# EXM_Safety_Board_-_Rev_A1.net
KiCad netlist of a schematic drawn in EAGLE
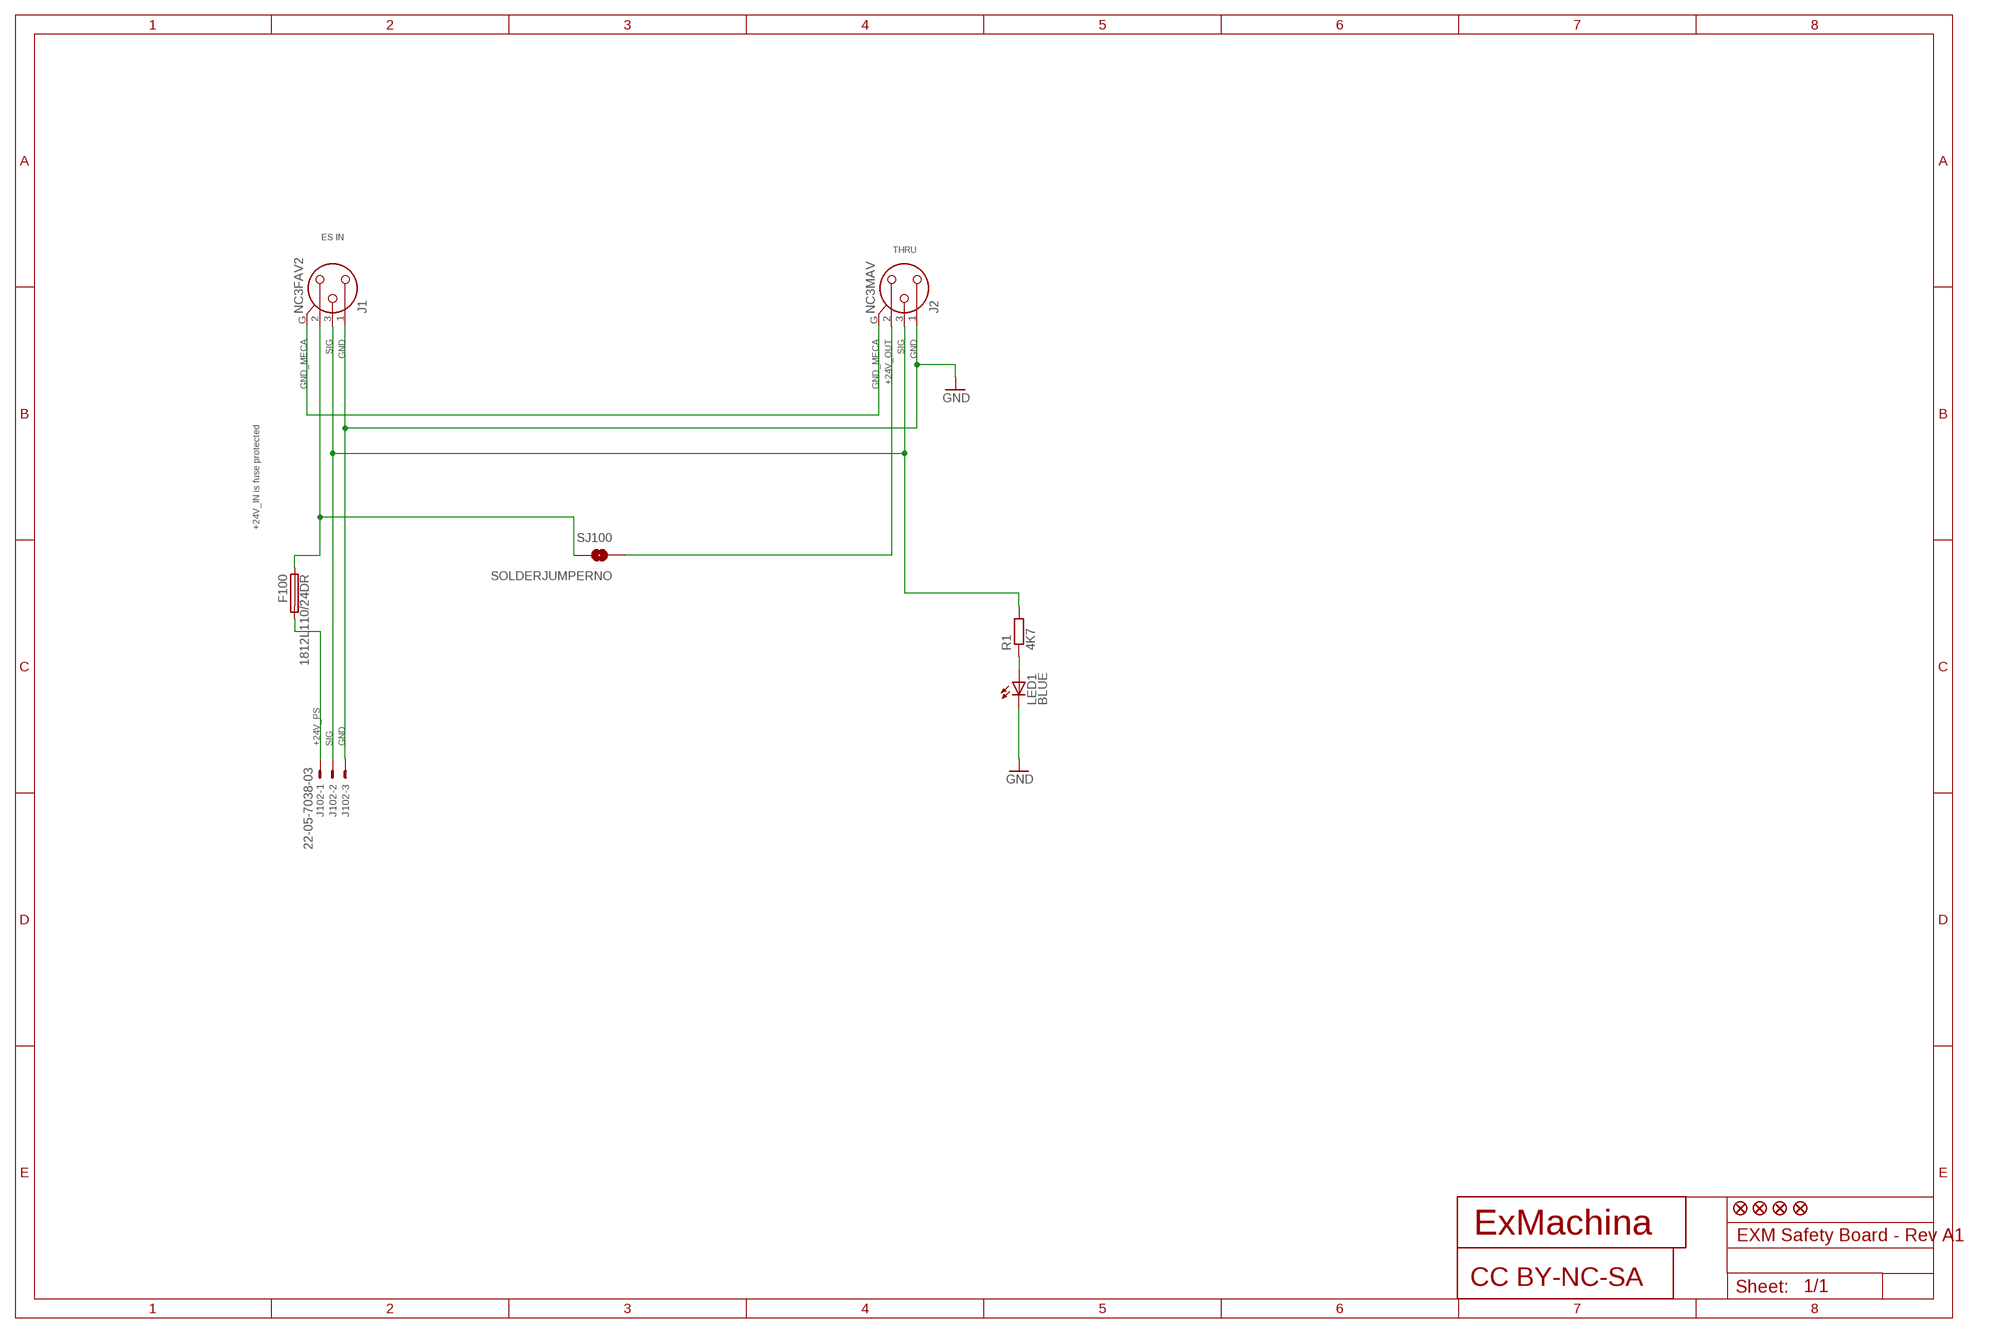
[diagram p0: schematic, sheet 1]

(export (version "E")
  (design (tool "Eeschema 10.0.6"))
  (components
    (comp (ref "CC100")
      (value "CC-BY-NC-SA")
      (footprint "eagle-import:CC-BY-NC-SA")
      (libsource (lib "eagle-import") (part "CC-BY-NC-SA"))
    )
    (comp (ref "F100")
      (value "1812L110/24DR")
      (footprint "eagle-import:LITTLEFUSE_SMD")
      (libsource (lib "eagle-import") (part "1812L110/24DR"))
    )
    (comp (ref "J1")
      (value "NC3FAV2")
      (footprint "eagle-import:NC3FAV2")
      (fields (field (name "MF") "NEUTRIK"))
      (libsource (lib "eagle-import") (part "NC3FAV2"))
    )
    (comp (ref "J2")
      (value "NC3MAV")
      (footprint "eagle-import:NC3MAV")
      (fields (field (name "MF") "FARNELL"))
      (libsource (lib "eagle-import") (part "NC3MAV"))
    )
    (comp (ref "J102")
      (value "22-05-7038-03")
      (footprint "eagle-import:7395-03")
      (libsource (lib "eagle-import") (part "22-?-0305-7038"))
    )
    (comp (ref "JP100")
      (value "FIDUCIAL1X2")
      (footprint "eagle-import:FIDUCIAL-1X2")
      (libsource (lib "eagle-import") (part "FIDUCIAL1X2"))
    )
    (comp (ref "JP101")
      (value "FIDUCIAL1X2")
      (footprint "eagle-import:FIDUCIAL-1X2")
      (libsource (lib "eagle-import") (part "FIDUCIAL1X2"))
    )
    (comp (ref "JP102")
      (value "FIDUCIAL1X2")
      (footprint "eagle-import:FIDUCIAL-1X2")
      (libsource (lib "eagle-import") (part "FIDUCIAL1X2"))
    )
    (comp (ref "JP103")
      (value "FIDUCIAL1X2")
      (footprint "eagle-import:FIDUCIAL-1X2")
      (libsource (lib "eagle-import") (part "FIDUCIAL1X2"))
    )
    (comp (ref "LED1")
      (value "BLUE")
      (footprint "eagle-import:CHIPLED_0603")
      (fields (field (name "MPN") "OVS-0603"))
      (libsource (lib "eagle-import") (part "LEDCHIPLED_0603"))
    )
    (comp (ref "R1")
      (value "4K7")
      (footprint "eagle-import:R0603")
      (fields (field (name "MPN") "RC0603FR-074K7L"))
      (libsource (lib "eagle-import") (part "R-EU_R0603"))
    )
    (comp (ref "SJ100")
      (value "SOLDERJUMPERNO")
      (footprint "eagle-import:SJ_2S-NO")
      (libsource (lib "eagle-import") (part "SOLDERJUMPERNO"))
    )
    (comp (ref "T100")
      (value "EXMACHINA-LOGO-NAME")
      (footprint "eagle-import:EXM-LOGO-BASELINE")
      (libsource (lib "eagle-import") (part "EXMACHINA-LOGO-NAME"))
    )
  )
  (nets
    (net (code "1") (name "/+24V_OUT") (class "Default")
      (node (ref "J2") (pin "2") (pinfunction "2_2") (pintype "passive"))
      (node (ref "SJ100") (pin "1") (pinfunction "1_1") (pintype "passive"))
    )
    (net (code "2") (name "/+24V_PS") (class "Default")
      (node (ref "F100") (pin "2") (pinfunction "2_2") (pintype "passive"))
      (node (ref "J102") (pin "1") (pinfunction "S_1") (pintype "passive"))
    )
    (net (code "3") (name "/GND_MECA") (class "Default")
      (node (ref "J1") (pin "G") (pinfunction "G_G") (pintype "passive"))
      (node (ref "J2") (pin "G") (pinfunction "G_G") (pintype "passive"))
    )
    (net (code "4") (name "/SIG") (class "Default")
      (node (ref "J1") (pin "3") (pinfunction "3_3") (pintype "passive"))
      (node (ref "J102") (pin "2") (pinfunction "S_2") (pintype "passive"))
      (node (ref "J2") (pin "3") (pinfunction "3_3") (pintype "passive"))
      (node (ref "R1") (pin "2") (pinfunction "2_2") (pintype "passive"))
    )
    (net (code "5") (name "GND") (class "Default")
      (node (ref "J1") (pin "1") (pinfunction "1_1") (pintype "passive"))
      (node (ref "J102") (pin "3") (pinfunction "S_3") (pintype "passive"))
      (node (ref "J2") (pin "1") (pinfunction "1_1") (pintype "passive"))
      (node (ref "LED1") (pin "C") (pinfunction "C_C") (pintype "passive"))
    )
    (net (code "6") (name "Net-(F100-Pad1)") (class "Default")
      (node (ref "F100") (pin "1") (pinfunction "1_1") (pintype "passive"))
      (node (ref "J1") (pin "2") (pinfunction "2_2") (pintype "passive"))
      (node (ref "SJ100") (pin "2") (pinfunction "2_2") (pintype "passive"))
    )
    (net (code "7") (name "Net-(LED1-PadA)") (class "Default")
      (node (ref "LED1") (pin "A") (pinfunction "A_A") (pintype "passive"))
      (node (ref "R1") (pin "1") (pinfunction "1_1") (pintype "passive"))
    )
  )
)
